# Ghetto_distortion_3_-_Pablo_Mart_n.net
KiCad netlist of a schematic drawn in EAGLE
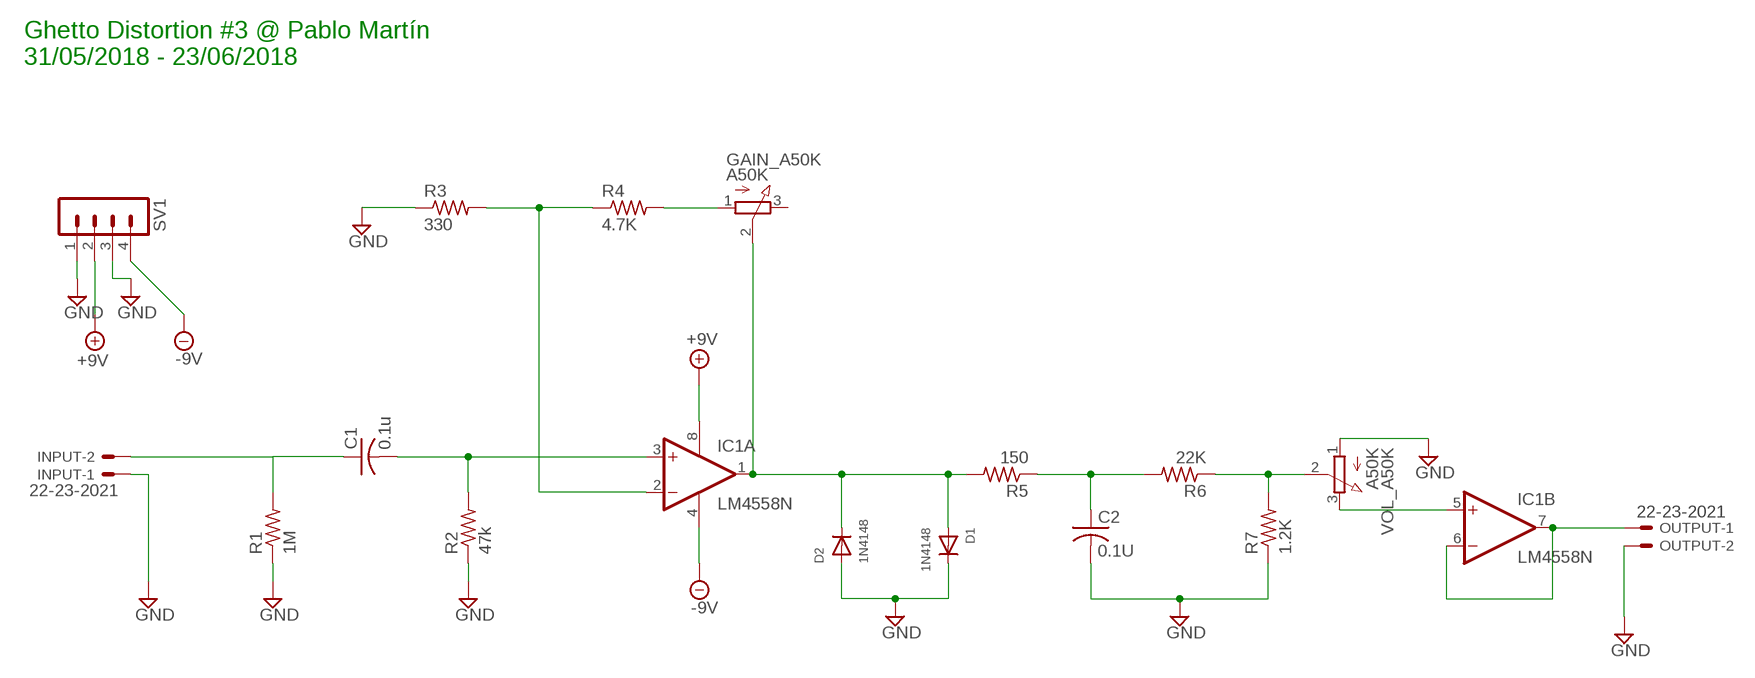
[diagram p0: schematic, sheet 1]

(export (version "E")
  (design (tool "Eeschema 10.0.6"))
  (components
    (comp (ref "C1")
      (value "0.1u")
      (footprint "eagle-import:C050-024X044")
      (libsource (lib "eagle-import") (part "C-US050-024X044"))
    )
    (comp (ref "C2")
      (value "0.1U")
      (footprint "eagle-import:C050-024X044")
      (libsource (lib "eagle-import") (part "C-US050-024X044"))
    )
    (comp (ref "D1")
      (value "1N4148")
      (footprint "eagle-import:DO-1N4148")
      (libsource (lib "eagle-import") (part "DIODEDO-1N4148"))
    )
    (comp (ref "D2")
      (value "1N4148")
      (footprint "eagle-import:DO-1N4148")
      (libsource (lib "eagle-import") (part "DIODEDO-1N4148"))
    )
    (comp (ref "GAIN_A50K")
      (value "A50K")
      (footprint "eagle-import:3RP_1610N")
      (libsource (lib "eagle-import") (part "3RP/1610N"))
    )
    (comp (ref "IC1")
      (value "LM4558N")
      (footprint "eagle-import:DIL08")
      (fields (field (name "SPICEPREFIX") "J"))
      (libsource (lib "eagle-import") (part "4558NLM"))
    )
    (comp (ref "INPUT")
      (value "22-23-2021")
      (footprint "eagle-import:22-23-2021")
      (fields (field (name "MF") "MOLEX"))
      (libsource (lib "eagle-import") (part "22-23-2021"))
    )
    (comp (ref "OUTPUT")
      (value "22-23-2021")
      (footprint "eagle-import:22-23-2021")
      (fields (field (name "MF") "MOLEX"))
      (libsource (lib "eagle-import") (part "22-23-2021"))
    )
    (comp (ref "R1")
      (value "1M")
      (footprint "eagle-import:0204_7")
      (libsource (lib "eagle-import") (part "R-US_0204/7"))
    )
    (comp (ref "R2")
      (value "47k")
      (footprint "eagle-import:0204_7")
      (libsource (lib "eagle-import") (part "R-US_0204/7"))
    )
    (comp (ref "R3")
      (value "330")
      (footprint "eagle-import:0204_7")
      (libsource (lib "eagle-import") (part "R-US_0204/7"))
    )
    (comp (ref "R4")
      (value "4.7K")
      (footprint "eagle-import:0204_7")
      (libsource (lib "eagle-import") (part "R-US_0204/7"))
    )
    (comp (ref "R5")
      (value "150")
      (footprint "eagle-import:0204_7")
      (libsource (lib "eagle-import") (part "R-US_0204/7"))
    )
    (comp (ref "R6")
      (value "22K")
      (footprint "eagle-import:0204_7")
      (libsource (lib "eagle-import") (part "R-US_0204/7"))
    )
    (comp (ref "R7")
      (value "1.2K")
      (footprint "eagle-import:0204_7")
      (libsource (lib "eagle-import") (part "R-US_0204/7"))
    )
    (comp (ref "SV1")
      (value "MA04-1")
      (footprint "eagle-import:MA04-1")
      (libsource (lib "eagle-import") (part "MA04-1"))
    )
    (comp (ref "VOL_A50K")
      (value "A50K")
      (footprint "eagle-import:3RP_1610N")
      (libsource (lib "eagle-import") (part "3RP/1610N"))
    )
  )
  (nets
    (net (code "1") (name "+9V") (class "Default")
      (node (ref "IC1") (pin "8") (pinfunction "V+_8") (pintype "power_in"))
      (node (ref "SV1") (pin "2") (pinfunction "2_2") (pintype "passive"))
    )
    (net (code "2") (name "-9V") (class "Default")
      (node (ref "IC1") (pin "4") (pinfunction "V-_4") (pintype "power_in"))
      (node (ref "SV1") (pin "4") (pinfunction "4_4") (pintype "passive"))
    )
    (net (code "3") (name "GND") (class "Default")
      (node (ref "C2") (pin "2") (pinfunction "2_2") (pintype "passive"))
      (node (ref "D1") (pin "C") (pinfunction "C_C") (pintype "passive"))
      (node (ref "D2") (pin "A") (pinfunction "A_A") (pintype "passive"))
      (node (ref "INPUT") (pin "1") (pinfunction "S_1") (pintype "passive"))
      (node (ref "OUTPUT") (pin "2") (pinfunction "S_2") (pintype "passive"))
      (node (ref "R1") (pin "1") (pinfunction "1_1") (pintype "passive"))
      (node (ref "R2") (pin "1") (pinfunction "1_1") (pintype "passive"))
      (node (ref "R3") (pin "1") (pinfunction "1_1") (pintype "passive"))
      (node (ref "R7") (pin "1") (pinfunction "1_1") (pintype "passive"))
      (node (ref "SV1") (pin "1") (pinfunction "1_1") (pintype "passive"))
      (node (ref "SV1") (pin "3") (pinfunction "3_3") (pintype "passive"))
      (node (ref "VOL_A50K") (pin "1") (pinfunction "A_1") (pintype "passive"))
    )
    (net (code "4") (name "Net-(C2-Pad1)") (class "Default")
      (node (ref "C2") (pin "1") (pinfunction "1_1") (pintype "passive"))
      (node (ref "R5") (pin "1") (pinfunction "1_1") (pintype "passive"))
      (node (ref "R6") (pin "2") (pinfunction "2_2") (pintype "passive"))
    )
    (net (code "5") (name "Net-(GAIN_A50K-A)") (class "Default")
      (node (ref "GAIN_A50K") (pin "1") (pinfunction "A_1") (pintype "passive"))
      (node (ref "R4") (pin "2") (pinfunction "2_2") (pintype "passive"))
    )
    (net (code "6") (name "Net-(GAIN_A50K-S)") (class "Default")
      (node (ref "D1") (pin "A") (pinfunction "A_A") (pintype "passive"))
      (node (ref "D2") (pin "C") (pinfunction "C_C") (pintype "passive"))
      (node (ref "GAIN_A50K") (pin "2") (pinfunction "S_2") (pintype "passive"))
      (node (ref "IC1") (pin "1") (pinfunction "OUT_1") (pintype "output"))
      (node (ref "R5") (pin "2") (pinfunction "2_2") (pintype "passive"))
    )
    (net (code "7") (name "Net-(IC1A-+IN)") (class "Default")
      (node (ref "C1") (pin "2") (pinfunction "2_2") (pintype "passive"))
      (node (ref "IC1") (pin "3") (pinfunction "+IN_3") (pintype "input"))
      (node (ref "R2") (pin "2") (pinfunction "2_2") (pintype "passive"))
    )
    (net (code "8") (name "Net-(IC1A--IN)") (class "Default")
      (node (ref "IC1") (pin "2") (pinfunction "-IN_2") (pintype "input"))
      (node (ref "R3") (pin "2") (pinfunction "2_2") (pintype "passive"))
      (node (ref "R4") (pin "1") (pinfunction "1_1") (pintype "passive"))
    )
    (net (code "9") (name "Net-(IC1B-+IN)") (class "Default")
      (node (ref "IC1") (pin "5") (pinfunction "+IN_5") (pintype "input"))
      (node (ref "VOL_A50K") (pin "3") (pinfunction "E_3") (pintype "passive"))
    )
    (net (code "10") (name "Net-(IC1B--IN)") (class "Default")
      (node (ref "IC1") (pin "6") (pinfunction "-IN_6") (pintype "input"))
      (node (ref "IC1") (pin "7") (pinfunction "OUT_7") (pintype "output"))
      (node (ref "OUTPUT") (pin "1") (pinfunction "S_1") (pintype "passive"))
    )
    (net (code "11") (name "Net-(INPUTB-S)") (class "Default")
      (node (ref "C1") (pin "1") (pinfunction "1_1") (pintype "passive"))
      (node (ref "INPUT") (pin "2") (pinfunction "S_2") (pintype "passive"))
      (node (ref "R1") (pin "2") (pinfunction "2_2") (pintype "passive"))
    )
    (net (code "12") (name "Net-(VOL_A50K-S)") (class "Default")
      (node (ref "R6") (pin "1") (pinfunction "1_1") (pintype "passive"))
      (node (ref "R7") (pin "2") (pinfunction "2_2") (pintype "passive"))
      (node (ref "VOL_A50K") (pin "2") (pinfunction "S_2") (pintype "passive"))
    )
    (net (code "13") (name "unconnected-(GAIN_A50K-E-Pad3)") (class "Default")
      (node (ref "GAIN_A50K") (pin "3") (pinfunction "E_3") (pintype "passive"))
    )
  )
)
